# adapter.net
KiCad netlist of a schematic drawn in EAGLE
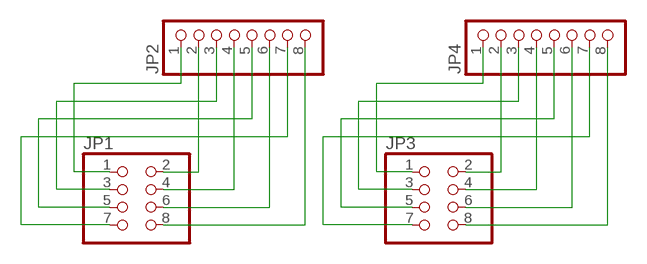
[diagram p0: schematic, sheet 1]

(export (version "E")
  (design (tool "Eeschema 10.0.6"))
  (components
    (comp (ref "JP1")
      (value "PINHD-2X4")
      (footprint "eagle-import:2X04")
      (libsource (lib "eagle-import") (part "PINHD-2X4"))
    )
    (comp (ref "JP2")
      (value "PINHD-1X8SMD_SMALL")
      (footprint "eagle-import:1X08_SMD_SMALL")
      (libsource (lib "eagle-import") (part "PINHD-1X8SMD_SMALL"))
    )
    (comp (ref "JP3")
      (value "PINHD-2X4")
      (footprint "eagle-import:2X04")
      (libsource (lib "eagle-import") (part "PINHD-2X4"))
    )
    (comp (ref "JP4")
      (value "PINHD-1X8SMD_SMALL")
      (footprint "eagle-import:1X08_SMD_SMALL")
      (libsource (lib "eagle-import") (part "PINHD-1X8SMD_SMALL"))
    )
  )
  (nets
    (net (code "1") (name "Net-(JP1-Pad1)") (class "Default")
      (node (ref "JP1") (pin "1") (pinfunction "1_1") (pintype "passive"))
      (node (ref "JP2") (pin "1") (pinfunction "1_1") (pintype "passive"))
    )
    (net (code "2") (name "Net-(JP1-Pad2)") (class "Default")
      (node (ref "JP1") (pin "2") (pinfunction "2_2") (pintype "passive"))
      (node (ref "JP2") (pin "2") (pinfunction "2_2") (pintype "passive"))
    )
    (net (code "3") (name "Net-(JP1-Pad3)") (class "Default")
      (node (ref "JP1") (pin "3") (pinfunction "3_3") (pintype "passive"))
      (node (ref "JP2") (pin "3") (pinfunction "3_3") (pintype "passive"))
    )
    (net (code "4") (name "Net-(JP1-Pad4)") (class "Default")
      (node (ref "JP1") (pin "4") (pinfunction "4_4") (pintype "passive"))
      (node (ref "JP2") (pin "4") (pinfunction "4_4") (pintype "passive"))
    )
    (net (code "5") (name "Net-(JP1-Pad5)") (class "Default")
      (node (ref "JP1") (pin "5") (pinfunction "5_5") (pintype "passive"))
      (node (ref "JP2") (pin "5") (pinfunction "5_5") (pintype "passive"))
    )
    (net (code "6") (name "Net-(JP1-Pad6)") (class "Default")
      (node (ref "JP1") (pin "6") (pinfunction "6_6") (pintype "passive"))
      (node (ref "JP2") (pin "6") (pinfunction "6_6") (pintype "passive"))
    )
    (net (code "7") (name "Net-(JP1-Pad7)") (class "Default")
      (node (ref "JP1") (pin "7") (pinfunction "7_7") (pintype "passive"))
      (node (ref "JP2") (pin "7") (pinfunction "7_7") (pintype "passive"))
    )
    (net (code "8") (name "Net-(JP1-Pad8)") (class "Default")
      (node (ref "JP1") (pin "8") (pinfunction "8_8") (pintype "passive"))
      (node (ref "JP2") (pin "8") (pinfunction "8_8") (pintype "passive"))
    )
    (net (code "9") (name "Net-(JP3-Pad1)") (class "Default")
      (node (ref "JP3") (pin "1") (pinfunction "1_1") (pintype "passive"))
      (node (ref "JP4") (pin "1") (pinfunction "1_1") (pintype "passive"))
    )
    (net (code "10") (name "Net-(JP3-Pad2)") (class "Default")
      (node (ref "JP3") (pin "2") (pinfunction "2_2") (pintype "passive"))
      (node (ref "JP4") (pin "2") (pinfunction "2_2") (pintype "passive"))
    )
    (net (code "11") (name "Net-(JP3-Pad3)") (class "Default")
      (node (ref "JP3") (pin "3") (pinfunction "3_3") (pintype "passive"))
      (node (ref "JP4") (pin "3") (pinfunction "3_3") (pintype "passive"))
    )
    (net (code "12") (name "Net-(JP3-Pad4)") (class "Default")
      (node (ref "JP3") (pin "4") (pinfunction "4_4") (pintype "passive"))
      (node (ref "JP4") (pin "4") (pinfunction "4_4") (pintype "passive"))
    )
    (net (code "13") (name "Net-(JP3-Pad5)") (class "Default")
      (node (ref "JP3") (pin "5") (pinfunction "5_5") (pintype "passive"))
      (node (ref "JP4") (pin "5") (pinfunction "5_5") (pintype "passive"))
    )
    (net (code "14") (name "Net-(JP3-Pad6)") (class "Default")
      (node (ref "JP3") (pin "6") (pinfunction "6_6") (pintype "passive"))
      (node (ref "JP4") (pin "6") (pinfunction "6_6") (pintype "passive"))
    )
    (net (code "15") (name "Net-(JP3-Pad7)") (class "Default")
      (node (ref "JP3") (pin "7") (pinfunction "7_7") (pintype "passive"))
      (node (ref "JP4") (pin "7") (pinfunction "7_7") (pintype "passive"))
    )
    (net (code "16") (name "Net-(JP3-Pad8)") (class "Default")
      (node (ref "JP3") (pin "8") (pinfunction "8_8") (pintype "passive"))
      (node (ref "JP4") (pin "8") (pinfunction "8_8") (pintype "passive"))
    )
  )
)
